# FreedomFighterPif.net
KiCad netlist of a schematic drawn in EAGLE
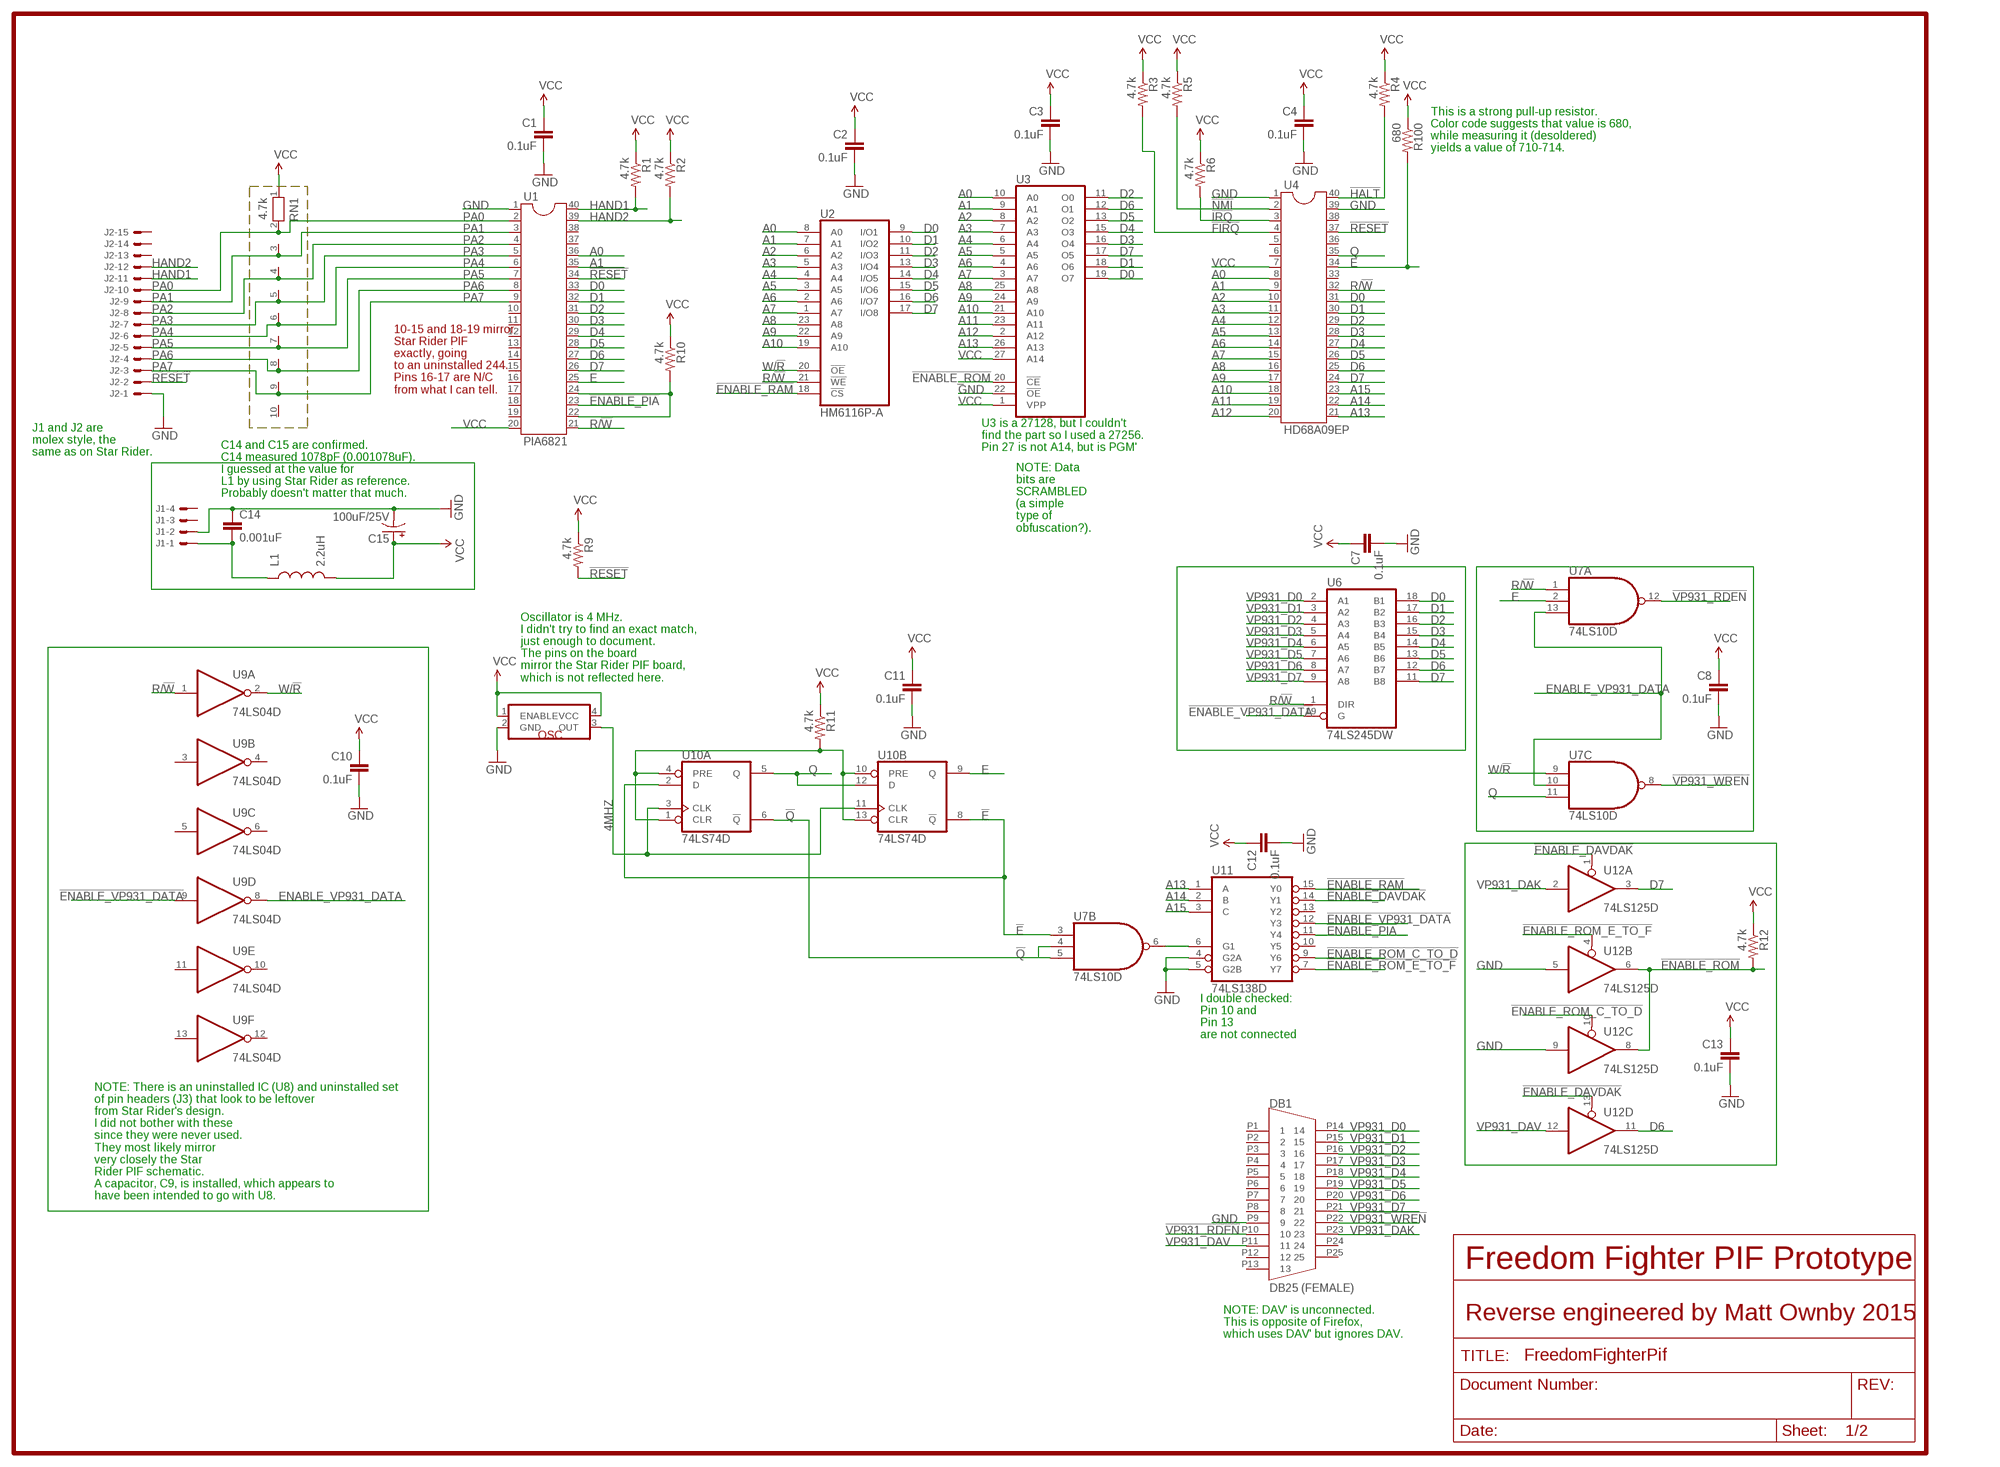
[diagram p0: schematic, sheet 1]
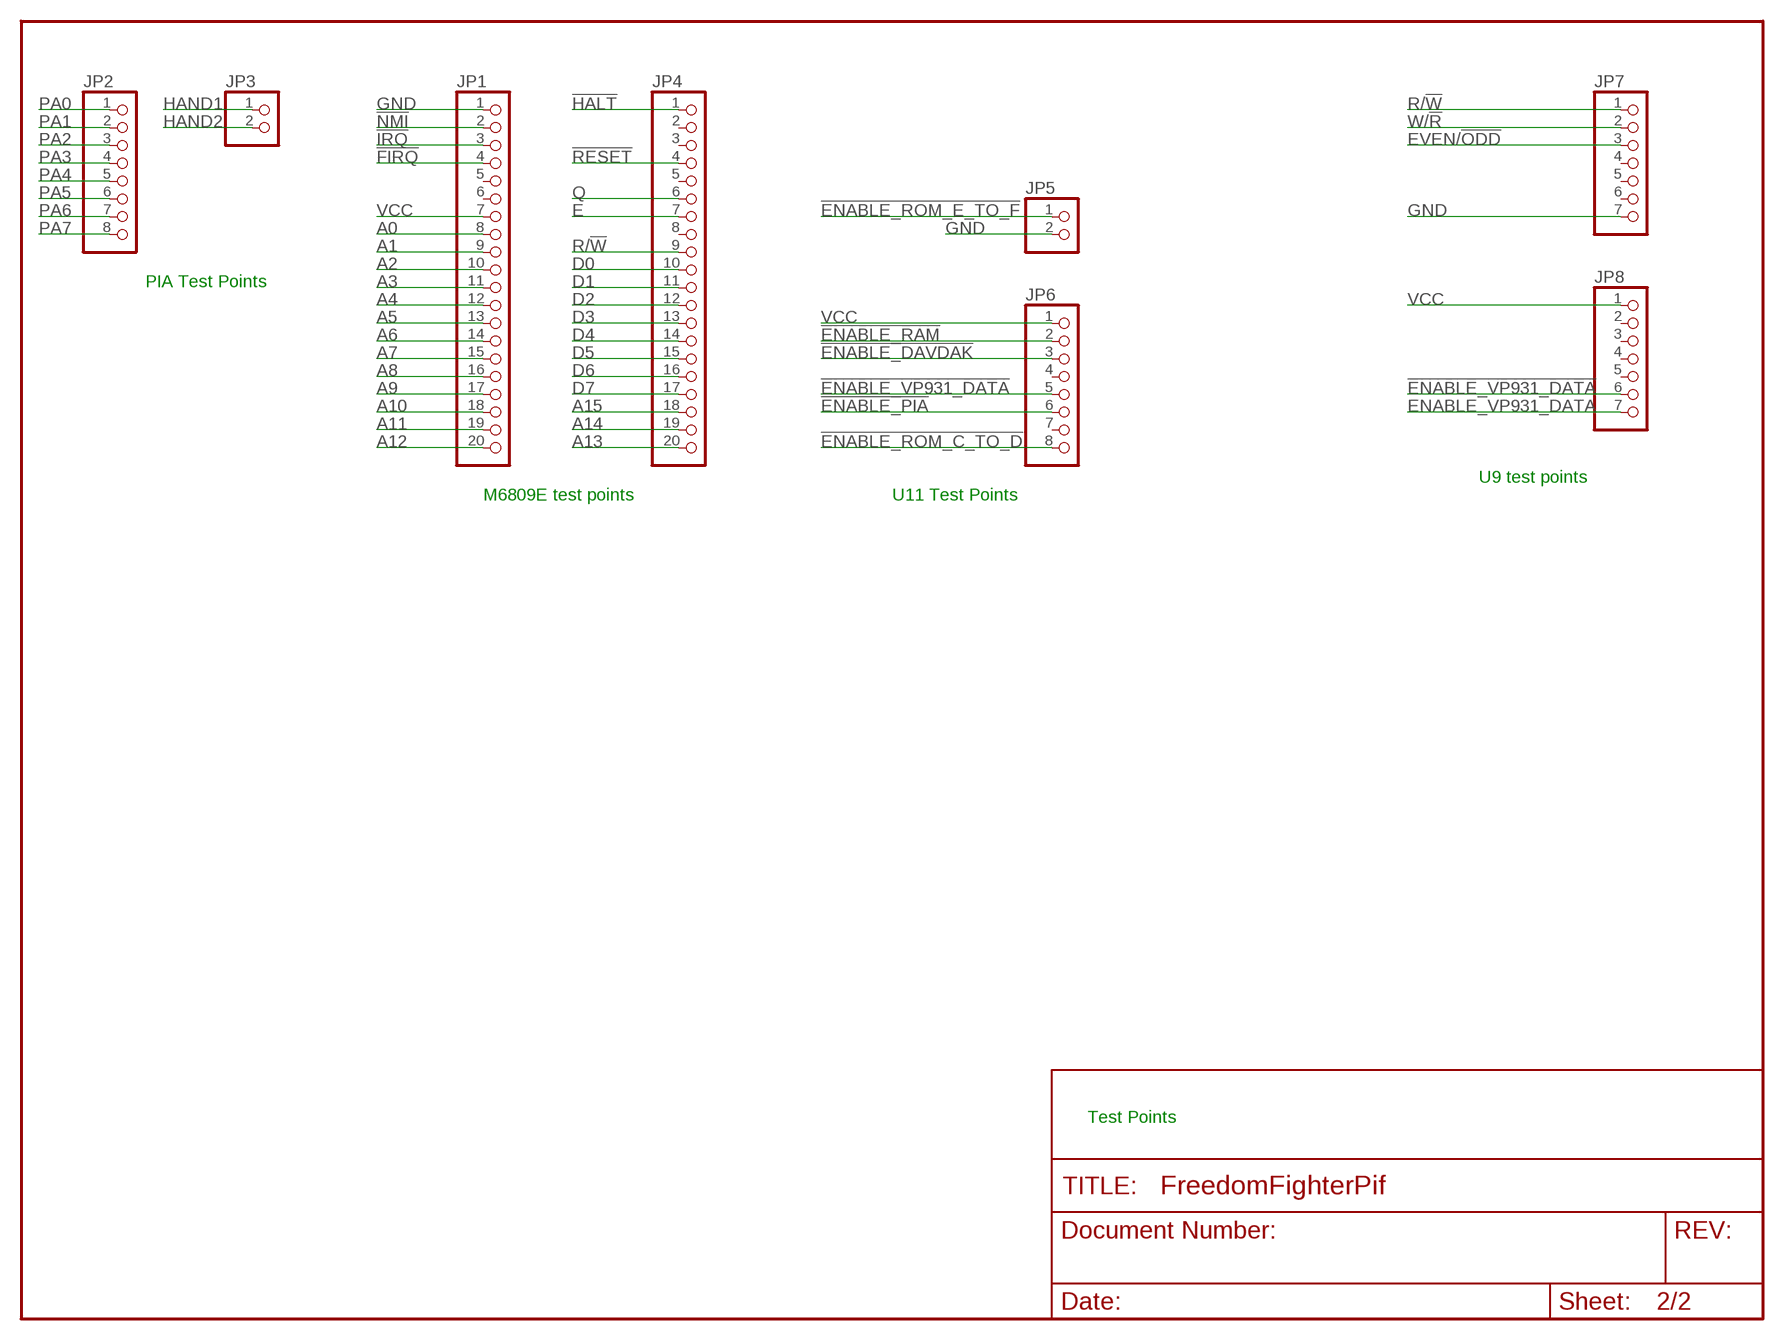
[diagram p1: schematic, sheet 2]

(export (version "E")
  (design (tool "Eeschema 10.0.6"))
  (components
    (comp (ref "JP1")
      (value "PINHD-1X20")
      (footprint "eagle-import:1X20")
      (libsource (lib "eagle-import") (part "PINHD-1X20"))
    )
    (comp (ref "JP2")
      (value "PINHD-1X8")
      (footprint "eagle-import:1X08")
      (libsource (lib "eagle-import") (part "PINHD-1X8"))
    )
    (comp (ref "JP3")
      (value "PINHD-1X2")
      (footprint "eagle-import:1X02")
      (libsource (lib "eagle-import") (part "PINHD-1X2"))
    )
    (comp (ref "JP4")
      (value "PINHD-1X20")
      (footprint "eagle-import:1X20")
      (libsource (lib "eagle-import") (part "PINHD-1X20"))
    )
    (comp (ref "JP5")
      (value "PINHD-1X2")
      (footprint "eagle-import:1X02")
      (libsource (lib "eagle-import") (part "PINHD-1X2"))
    )
    (comp (ref "JP6")
      (value "PINHD-1X8")
      (footprint "eagle-import:1X08")
      (libsource (lib "eagle-import") (part "PINHD-1X8"))
    )
    (comp (ref "JP7")
      (value "PINHD-1X7")
      (footprint "eagle-import:1X07")
      (libsource (lib "eagle-import") (part "PINHD-1X7"))
    )
    (comp (ref "JP8")
      (value "PINHD-1X7")
      (footprint "eagle-import:1X07")
      (libsource (lib "eagle-import") (part "PINHD-1X7"))
    )
    (comp (ref "C1")
      (value "0.1uF")
      (footprint "eagle-import:1206")
      (libsource (lib "eagle-import") (part "CAP1206"))
    )
    (comp (ref "C2")
      (value "0.1uF")
      (footprint "eagle-import:1206")
      (libsource (lib "eagle-import") (part "CAP1206"))
    )
    (comp (ref "C3")
      (value "0.1uF")
      (footprint "eagle-import:1206")
      (libsource (lib "eagle-import") (part "CAP1206"))
    )
    (comp (ref "C4")
      (value "0.1uF")
      (footprint "eagle-import:1206")
      (libsource (lib "eagle-import") (part "CAP1206"))
    )
    (comp (ref "C7")
      (value "0.1uF")
      (footprint "eagle-import:1206")
      (libsource (lib "eagle-import") (part "CAP1206"))
    )
    (comp (ref "C8")
      (value "0.1uF")
      (footprint "eagle-import:1206")
      (libsource (lib "eagle-import") (part "CAP1206"))
    )
    (comp (ref "C10")
      (value "0.1uF")
      (footprint "eagle-import:1206")
      (libsource (lib "eagle-import") (part "CAP1206"))
    )
    (comp (ref "C11")
      (value "0.1uF")
      (footprint "eagle-import:1206")
      (libsource (lib "eagle-import") (part "CAP1206"))
    )
    (comp (ref "C12")
      (value "0.1uF")
      (footprint "eagle-import:1206")
      (libsource (lib "eagle-import") (part "CAP1206"))
    )
    (comp (ref "C13")
      (value "0.1uF")
      (footprint "eagle-import:1206")
      (libsource (lib "eagle-import") (part "CAP1206"))
    )
    (comp (ref "C14")
      (value "0.001uF")
      (footprint "eagle-import:1206")
      (libsource (lib "eagle-import") (part "CAP1206"))
    )
    (comp (ref "C15")
      (value "100uF/25V")
      (footprint "eagle-import:CPOL-RADIAL-10UF-25V")
      (libsource (lib "eagle-import") (part "CAP_POLPTH2"))
    )
    (comp (ref "DB1")
      (value "DB25 (FEMALE)")
      (footprint "eagle-import:A32077-ND")
      (libsource (lib "eagle-import") (part "A32077-ND"))
    )
    (comp (ref "J1")
      (value "KK-156-4")
      (footprint "eagle-import:KK-156-4")
      (libsource (lib "eagle-import") (part "KK-156-4"))
    )
    (comp (ref "J2")
      (value "KK-156-15")
      (footprint "eagle-import:KK-156-15")
      (libsource (lib "eagle-import") (part "KK-156-15"))
    )
    (comp (ref "L1")
      (value "2.2uH")
      (footprint "eagle-import:INDUCTOR-1206")
      (libsource (lib "eagle-import") (part "INDUCTORH1206"))
    )
    (comp (ref "R1")
      (value "4.7k")
      (footprint "eagle-import:1206")
      (libsource (lib "eagle-import") (part "RESISTOR1206"))
    )
    (comp (ref "R2")
      (value "4.7k")
      (footprint "eagle-import:1206")
      (libsource (lib "eagle-import") (part "RESISTOR1206"))
    )
    (comp (ref "R3")
      (value "4.7k")
      (footprint "eagle-import:1206")
      (libsource (lib "eagle-import") (part "RESISTOR1206"))
    )
    (comp (ref "R4")
      (value "4.7k")
      (footprint "eagle-import:1206")
      (libsource (lib "eagle-import") (part "RESISTOR1206"))
    )
    (comp (ref "R5")
      (value "4.7k")
      (footprint "eagle-import:1206")
      (libsource (lib "eagle-import") (part "RESISTOR1206"))
    )
    (comp (ref "R6")
      (value "4.7k")
      (footprint "eagle-import:1206")
      (libsource (lib "eagle-import") (part "RESISTOR1206"))
    )
    (comp (ref "R9")
      (value "4.7k")
      (footprint "eagle-import:1206")
      (libsource (lib "eagle-import") (part "RESISTOR1206"))
    )
    (comp (ref "R10")
      (value "4.7k")
      (footprint "eagle-import:1206")
      (libsource (lib "eagle-import") (part "RESISTOR1206"))
    )
    (comp (ref "R11")
      (value "4.7k")
      (footprint "eagle-import:1206")
      (libsource (lib "eagle-import") (part "RESISTOR1206"))
    )
    (comp (ref "R12")
      (value "4.7k")
      (footprint "eagle-import:1206")
      (libsource (lib "eagle-import") (part "RESISTOR1206"))
    )
    (comp (ref "R100")
      (value "680")
      (footprint "eagle-import:1206")
      (libsource (lib "eagle-import") (part "RESISTOR1206"))
    )
    (comp (ref "RN1")
      (value "4.7k")
      (footprint "eagle-import:RN-10")
      (libsource (lib "eagle-import") (part "RN09"))
    )
    (comp (ref "U$1")
      (value "OSCILLATOR-SMT4")
      (footprint "eagle-import:SMT4-7MMX5MM")
      (libsource (lib "eagle-import") (part "OSCILLATOR-SMT4"))
    )
    (comp (ref "U1")
      (value "PIA6821")
      (footprint "eagle-import:DIL40")
      (libsource (lib "eagle-import") (part "DIL40"))
    )
    (comp (ref "U2")
      (value "HM6116P-A")
      (footprint "eagle-import:SO24-2")
      (libsource (lib "eagle-import") (part "6116S"))
    )
    (comp (ref "U3")
      (value "27256")
      (footprint "eagle-import:DIL28")
      (libsource (lib "eagle-import") (part "27256"))
    )
    (comp (ref "U4")
      (value "HD68A09EP")
      (footprint "eagle-import:DIL40")
      (libsource (lib "eagle-import") (part "DIL40"))
    )
    (comp (ref "U6")
      (value "74LS245DW")
      (footprint "eagle-import:SO20W")
      (libsource (lib "eagle-import") (part "74245DWLS"))
    )
    (comp (ref "U7")
      (value "74LS10D")
      (footprint "eagle-import:SO14")
      (libsource (lib "eagle-import") (part "7410DLS"))
    )
    (comp (ref "U9")
      (value "74LS04D")
      (footprint "eagle-import:SO14")
      (libsource (lib "eagle-import") (part "7404DLS"))
    )
    (comp (ref "U10")
      (value "74LS74D")
      (footprint "eagle-import:SO14")
      (libsource (lib "eagle-import") (part "7474DLS"))
    )
    (comp (ref "U11")
      (value "74LS138D")
      (footprint "eagle-import:SO16")
      (libsource (lib "eagle-import") (part "74138DLS"))
    )
    (comp (ref "U12")
      (value "74LS125D")
      (footprint "eagle-import:SO14")
      (libsource (lib "eagle-import") (part "74125DLS"))
    )
  )
  (nets
    (net (code "1") (name "4MHZ") (class "Default")
      (node (ref "U$1") (pin "3") (pinfunction "OUT_3") (pintype "output"))
      (node (ref "U10") (pin "11") (pinfunction "CLK_11") (pintype "input"))
      (node (ref "U10") (pin "3") (pinfunction "CLK_3") (pintype "input"))
    )
    (net (code "2") (name "A0") (class "Default")
      (node (ref "JP1") (pin "8") (pinfunction "8_8") (pintype "passive"))
      (node (ref "U1") (pin "36") (pinfunction "36_36") (pintype "passive"))
      (node (ref "U2") (pin "8") (pinfunction "A0_8") (pintype "input"))
      (node (ref "U3") (pin "10") (pinfunction "A0_10") (pintype "input"))
      (node (ref "U4") (pin "8") (pinfunction "8_8") (pintype "passive"))
    )
    (net (code "3") (name "A1") (class "Default")
      (node (ref "JP1") (pin "9") (pinfunction "9_9") (pintype "passive"))
      (node (ref "U1") (pin "35") (pinfunction "35_35") (pintype "passive"))
      (node (ref "U2") (pin "7") (pinfunction "A1_7") (pintype "input"))
      (node (ref "U3") (pin "9") (pinfunction "A1_9") (pintype "input"))
      (node (ref "U4") (pin "9") (pinfunction "9_9") (pintype "passive"))
    )
    (net (code "4") (name "A2") (class "Default")
      (node (ref "JP1") (pin "10") (pinfunction "10_10") (pintype "passive"))
      (node (ref "U2") (pin "6") (pinfunction "A2_6") (pintype "input"))
      (node (ref "U3") (pin "8") (pinfunction "A2_8") (pintype "input"))
      (node (ref "U4") (pin "10") (pinfunction "10_10") (pintype "passive"))
    )
    (net (code "5") (name "A3") (class "Default")
      (node (ref "JP1") (pin "11") (pinfunction "11_11") (pintype "passive"))
      (node (ref "U2") (pin "5") (pinfunction "A3_5") (pintype "input"))
      (node (ref "U3") (pin "7") (pinfunction "A3_7") (pintype "input"))
      (node (ref "U4") (pin "11") (pinfunction "11_11") (pintype "passive"))
    )
    (net (code "6") (name "A4") (class "Default")
      (node (ref "JP1") (pin "12") (pinfunction "12_12") (pintype "passive"))
      (node (ref "U2") (pin "4") (pinfunction "A4_4") (pintype "input"))
      (node (ref "U3") (pin "6") (pinfunction "A4_6") (pintype "input"))
      (node (ref "U4") (pin "12") (pinfunction "12_12") (pintype "passive"))
    )
    (net (code "7") (name "A5") (class "Default")
      (node (ref "JP1") (pin "13") (pinfunction "13_13") (pintype "passive"))
      (node (ref "U2") (pin "3") (pinfunction "A5_3") (pintype "input"))
      (node (ref "U3") (pin "5") (pinfunction "A5_5") (pintype "input"))
      (node (ref "U4") (pin "13") (pinfunction "13_13") (pintype "passive"))
    )
    (net (code "8") (name "A6") (class "Default")
      (node (ref "JP1") (pin "14") (pinfunction "14_14") (pintype "passive"))
      (node (ref "U2") (pin "2") (pinfunction "A6_2") (pintype "input"))
      (node (ref "U3") (pin "4") (pinfunction "A6_4") (pintype "input"))
      (node (ref "U4") (pin "14") (pinfunction "14_14") (pintype "passive"))
    )
    (net (code "9") (name "A7") (class "Default")
      (node (ref "JP1") (pin "15") (pinfunction "15_15") (pintype "passive"))
      (node (ref "U2") (pin "1") (pinfunction "A7_1") (pintype "input"))
      (node (ref "U3") (pin "3") (pinfunction "A7_3") (pintype "input"))
      (node (ref "U4") (pin "15") (pinfunction "15_15") (pintype "passive"))
    )
    (net (code "10") (name "A8") (class "Default")
      (node (ref "JP1") (pin "16") (pinfunction "16_16") (pintype "passive"))
      (node (ref "U2") (pin "23") (pinfunction "A8_23") (pintype "input"))
      (node (ref "U3") (pin "25") (pinfunction "A8_25") (pintype "input"))
      (node (ref "U4") (pin "16") (pinfunction "16_16") (pintype "passive"))
    )
    (net (code "11") (name "A9") (class "Default")
      (node (ref "JP1") (pin "17") (pinfunction "17_17") (pintype "passive"))
      (node (ref "U2") (pin "22") (pinfunction "A9_22") (pintype "input"))
      (node (ref "U3") (pin "24") (pinfunction "A9_24") (pintype "input"))
      (node (ref "U4") (pin "17") (pinfunction "17_17") (pintype "passive"))
    )
    (net (code "12") (name "A10") (class "Default")
      (node (ref "JP1") (pin "18") (pinfunction "18_18") (pintype "passive"))
      (node (ref "U2") (pin "19") (pinfunction "A10_19") (pintype "input"))
      (node (ref "U3") (pin "21") (pinfunction "A10_21") (pintype "input"))
      (node (ref "U4") (pin "18") (pinfunction "18_18") (pintype "passive"))
    )
    (net (code "13") (name "A11") (class "Default")
      (node (ref "JP1") (pin "19") (pinfunction "19_19") (pintype "passive"))
      (node (ref "U3") (pin "23") (pinfunction "A11_23") (pintype "input"))
      (node (ref "U4") (pin "19") (pinfunction "19_19") (pintype "passive"))
    )
    (net (code "14") (name "A12") (class "Default")
      (node (ref "JP1") (pin "20") (pinfunction "20_20") (pintype "passive"))
      (node (ref "U3") (pin "2") (pinfunction "A12_2") (pintype "input"))
      (node (ref "U4") (pin "20") (pinfunction "20_20") (pintype "passive"))
    )
    (net (code "15") (name "A13") (class "Default")
      (node (ref "JP4") (pin "20") (pinfunction "20_20") (pintype "passive"))
      (node (ref "U11") (pin "1") (pinfunction "A_1") (pintype "input"))
      (node (ref "U3") (pin "26") (pinfunction "A13_26") (pintype "input"))
      (node (ref "U4") (pin "21") (pinfunction "21_21") (pintype "passive"))
    )
    (net (code "16") (name "A14") (class "Default")
      (node (ref "JP4") (pin "19") (pinfunction "19_19") (pintype "passive"))
      (node (ref "U11") (pin "2") (pinfunction "B_2") (pintype "input"))
      (node (ref "U4") (pin "22") (pinfunction "22_22") (pintype "passive"))
    )
    (net (code "17") (name "A15") (class "Default")
      (node (ref "JP4") (pin "18") (pinfunction "18_18") (pintype "passive"))
      (node (ref "U11") (pin "3") (pinfunction "C_3") (pintype "input"))
      (node (ref "U4") (pin "23") (pinfunction "23_23") (pintype "passive"))
    )
    (net (code "18") (name "D0") (class "Default")
      (node (ref "JP4") (pin "10") (pinfunction "10_10") (pintype "passive"))
      (node (ref "U1") (pin "33") (pinfunction "33_33") (pintype "passive"))
      (node (ref "U2") (pin "9") (pinfunction "I/O1_9") (pintype "bidirectional"))
      (node (ref "U3") (pin "19") (pinfunction "O7_19") (pintype "tri_state"))
      (node (ref "U4") (pin "31") (pinfunction "31_31") (pintype "passive"))
      (node (ref "U6") (pin "18") (pinfunction "B1_18") (pintype "bidirectional"))
    )
    (net (code "19") (name "D1") (class "Default")
      (node (ref "JP4") (pin "11") (pinfunction "11_11") (pintype "passive"))
      (node (ref "U1") (pin "32") (pinfunction "32_32") (pintype "passive"))
      (node (ref "U2") (pin "10") (pinfunction "I/O2_10") (pintype "bidirectional"))
      (node (ref "U3") (pin "18") (pinfunction "O6_18") (pintype "tri_state"))
      (node (ref "U4") (pin "30") (pinfunction "30_30") (pintype "passive"))
      (node (ref "U6") (pin "17") (pinfunction "B2_17") (pintype "bidirectional"))
    )
    (net (code "20") (name "D2") (class "Default")
      (node (ref "JP4") (pin "12") (pinfunction "12_12") (pintype "passive"))
      (node (ref "U1") (pin "31") (pinfunction "31_31") (pintype "passive"))
      (node (ref "U2") (pin "11") (pinfunction "I/O3_11") (pintype "bidirectional"))
      (node (ref "U3") (pin "11") (pinfunction "O0_11") (pintype "tri_state"))
      (node (ref "U4") (pin "29") (pinfunction "29_29") (pintype "passive"))
      (node (ref "U6") (pin "16") (pinfunction "B3_16") (pintype "bidirectional"))
    )
    (net (code "21") (name "D3") (class "Default")
      (node (ref "JP4") (pin "13") (pinfunction "13_13") (pintype "passive"))
      (node (ref "U1") (pin "30") (pinfunction "30_30") (pintype "passive"))
      (node (ref "U2") (pin "13") (pinfunction "I/O4_13") (pintype "bidirectional"))
      (node (ref "U3") (pin "16") (pinfunction "O4_16") (pintype "tri_state"))
      (node (ref "U4") (pin "28") (pinfunction "28_28") (pintype "passive"))
      (node (ref "U6") (pin "15") (pinfunction "B4_15") (pintype "bidirectional"))
    )
    (net (code "22") (name "D4") (class "Default")
      (node (ref "JP4") (pin "14") (pinfunction "14_14") (pintype "passive"))
      (node (ref "U1") (pin "29") (pinfunction "29_29") (pintype "passive"))
      (node (ref "U2") (pin "14") (pinfunction "I/O5_14") (pintype "bidirectional"))
      (node (ref "U3") (pin "15") (pinfunction "O3_15") (pintype "tri_state"))
      (node (ref "U4") (pin "27") (pinfunction "27_27") (pintype "passive"))
      (node (ref "U6") (pin "14") (pinfunction "B5_14") (pintype "bidirectional"))
    )
    (net (code "23") (name "D5") (class "Default")
      (node (ref "JP4") (pin "15") (pinfunction "15_15") (pintype "passive"))
      (node (ref "U1") (pin "28") (pinfunction "28_28") (pintype "passive"))
      (node (ref "U2") (pin "15") (pinfunction "I/O6_15") (pintype "bidirectional"))
      (node (ref "U3") (pin "13") (pinfunction "O2_13") (pintype "tri_state"))
      (node (ref "U4") (pin "26") (pinfunction "26_26") (pintype "passive"))
      (node (ref "U6") (pin "13") (pinfunction "B6_13") (pintype "bidirectional"))
    )
    (net (code "24") (name "D6") (class "Default")
      (node (ref "JP4") (pin "16") (pinfunction "16_16") (pintype "passive"))
      (node (ref "U1") (pin "27") (pinfunction "27_27") (pintype "passive"))
      (node (ref "U12") (pin "11") (pinfunction "O_11") (pintype "tri_state"))
      (node (ref "U2") (pin "16") (pinfunction "I/O7_16") (pintype "bidirectional"))
      (node (ref "U3") (pin "12") (pinfunction "O1_12") (pintype "tri_state"))
      (node (ref "U4") (pin "25") (pinfunction "25_25") (pintype "passive"))
      (node (ref "U6") (pin "12") (pinfunction "B7_12") (pintype "bidirectional"))
    )
    (net (code "25") (name "D7") (class "Default")
      (node (ref "JP4") (pin "17") (pinfunction "17_17") (pintype "passive"))
      (node (ref "U1") (pin "26") (pinfunction "26_26") (pintype "passive"))
      (node (ref "U12") (pin "3") (pinfunction "O_3") (pintype "tri_state"))
      (node (ref "U2") (pin "17") (pinfunction "I/O8_17") (pintype "bidirectional"))
      (node (ref "U3") (pin "17") (pinfunction "O5_17") (pintype "tri_state"))
      (node (ref "U4") (pin "24") (pinfunction "24_24") (pintype "passive"))
      (node (ref "U6") (pin "11") (pinfunction "B8_11") (pintype "bidirectional"))
    )
    (net (code "26") (name "E") (class "Default")
      (node (ref "JP4") (pin "7") (pinfunction "7_7") (pintype "passive"))
      (node (ref "R100") (pin "2") (pinfunction "2_2") (pintype "passive"))
      (node (ref "U1") (pin "25") (pinfunction "25_25") (pintype "passive"))
      (node (ref "U10") (pin "9") (pinfunction "Q_9") (pintype "output"))
      (node (ref "U4") (pin "34") (pinfunction "34_34") (pintype "passive"))
      (node (ref "U7") (pin "2") (pinfunction "I1_2") (pintype "input"))
    )
    (net (code "27") (name "ENABLE_VP931_DATA") (class "Default")
      (node (ref "JP8") (pin "7") (pinfunction "7_7") (pintype "passive"))
      (node (ref "U7") (pin "10") (pinfunction "I1_10") (pintype "input"))
      (node (ref "U7") (pin "13") (pinfunction "I2_13") (pintype "input"))
      (node (ref "U9") (pin "8") (pinfunction "O_8") (pintype "output"))
    )
    (net (code "28") (name "EVEN{slash}~{ODD}") (class "Default")
      (node (ref "JP7") (pin "3") (pinfunction "3_3") (pintype "passive"))
    )
    (net (code "29") (name "GND") (class "Default")
      (node (ref "C1") (pin "2") (pinfunction "2_2") (pintype "passive"))
      (node (ref "C10") (pin "2") (pinfunction "2_2") (pintype "passive"))
      (node (ref "C11") (pin "2") (pinfunction "2_2") (pintype "passive"))
      (node (ref "C12") (pin "2") (pinfunction "2_2") (pintype "passive"))
      (node (ref "C13") (pin "2") (pinfunction "2_2") (pintype "passive"))
      (node (ref "C14") (pin "1") (pinfunction "1_1") (pintype "passive"))
      (node (ref "C15") (pin "2") (pinfunction "-_2") (pintype "passive"))
      (node (ref "C2") (pin "2") (pinfunction "2_2") (pintype "passive"))
      (node (ref "C3") (pin "2") (pinfunction "2_2") (pintype "passive"))
      (node (ref "C4") (pin "2") (pinfunction "2_2") (pintype "passive"))
      (node (ref "C7") (pin "2") (pinfunction "2_2") (pintype "passive"))
      (node (ref "C8") (pin "2") (pinfunction "2_2") (pintype "passive"))
      (node (ref "DB1") (pin "P9") (pinfunction "9_P9") (pintype "bidirectional"))
      (node (ref "J1") (pin "2") (pinfunction "S_2") (pintype "passive"))
      (node (ref "J2") (pin "1") (pinfunction "S_1") (pintype "passive"))
      (node (ref "JP1") (pin "1") (pinfunction "1_1") (pintype "passive"))
      (node (ref "JP5") (pin "2") (pinfunction "2_2") (pintype "passive"))
      (node (ref "JP7") (pin "7") (pinfunction "7_7") (pintype "passive"))
      (node (ref "U$1") (pin "2") (pinfunction "GND_2") (pintype "power_in"))
      (node (ref "U1") (pin "1") (pinfunction "1_1") (pintype "passive"))
      (node (ref "U11") (pin "4") (pinfunction "G2A_4") (pintype "input"))
      (node (ref "U11") (pin "5") (pinfunction "G2B_5") (pintype "input"))
      (node (ref "U12") (pin "5") (pinfunction "I_5") (pintype "input"))
      (node (ref "U12") (pin "9") (pinfunction "I_9") (pintype "input"))
      (node (ref "U3") (pin "22") (pinfunction "~{OE}_22") (pintype "input"))
      (node (ref "U4") (pin "1") (pinfunction "1_1") (pintype "passive"))
      (node (ref "U4") (pin "39") (pinfunction "39_39") (pintype "passive"))
    )
    (net (code "30") (name "HAND1") (class "Default")
      (node (ref "J2") (pin "11") (pinfunction "S_11") (pintype "passive"))
      (node (ref "JP3") (pin "1") (pinfunction "1_1") (pintype "passive"))
      (node (ref "R1") (pin "2") (pinfunction "2_2") (pintype "passive"))
      (node (ref "U1") (pin "40") (pinfunction "40_40") (pintype "passive"))
    )
    (net (code "31") (name "HAND2") (class "Default")
      (node (ref "J2") (pin "12") (pinfunction "S_12") (pintype "passive"))
      (node (ref "JP3") (pin "2") (pinfunction "2_2") (pintype "passive"))
      (node (ref "R2") (pin "2") (pinfunction "2_2") (pintype "passive"))
      (node (ref "U1") (pin "39") (pinfunction "39_39") (pintype "passive"))
    )
    (net (code "32") (name "Net-(J1A-S)") (class "Default")
      (node (ref "C14") (pin "2") (pinfunction "2_2") (pintype "passive"))
      (node (ref "J1") (pin "1") (pinfunction "S_1") (pintype "passive"))
      (node (ref "L1") (pin "P$1") (pinfunction "1_P$1") (pintype "passive"))
    )
    (net (code "33") (name "Net-(R10-Pad2)") (class "Default")
      (node (ref "R10") (pin "2") (pinfunction "2_2") (pintype "passive"))
      (node (ref "U1") (pin "22") (pinfunction "22_22") (pintype "passive"))
      (node (ref "U1") (pin "24") (pinfunction "24_24") (pintype "passive"))
    )
    (net (code "34") (name "Net-(U10A-CLR)") (class "Default")
      (node (ref "R11") (pin "2") (pinfunction "2_2") (pintype "passive"))
      (node (ref "U10") (pin "1") (pinfunction "CLR_1") (pintype "input"))
      (node (ref "U10") (pin "10") (pinfunction "PRE_10") (pintype "input"))
      (node (ref "U10") (pin "13") (pinfunction "CLR_13") (pintype "input"))
      (node (ref "U10") (pin "4") (pinfunction "PRE_4") (pintype "input"))
    )
    (net (code "35") (name "Net-(U11A-G1)") (class "Default")
      (node (ref "U11") (pin "6") (pinfunction "G1_6") (pintype "input"))
      (node (ref "U7") (pin "6") (pinfunction "O_6") (pintype "output"))
    )
    (net (code "36") (name "PA0") (class "Default")
      (node (ref "J2") (pin "10") (pinfunction "S_10") (pintype "passive"))
      (node (ref "JP2") (pin "1") (pinfunction "1_1") (pintype "passive"))
      (node (ref "RN1") (pin "2") (pinfunction "2_2") (pintype "passive"))
      (node (ref "U1") (pin "2") (pinfunction "2_2") (pintype "passive"))
    )
    (net (code "37") (name "PA1") (class "Default")
      (node (ref "J2") (pin "9") (pinfunction "S_9") (pintype "passive"))
      (node (ref "JP2") (pin "2") (pinfunction "2_2") (pintype "passive"))
      (node (ref "RN1") (pin "3") (pinfunction "3_3") (pintype "passive"))
      (node (ref "U1") (pin "3") (pinfunction "3_3") (pintype "passive"))
    )
    (net (code "38") (name "PA2") (class "Default")
      (node (ref "J2") (pin "8") (pinfunction "S_8") (pintype "passive"))
      (node (ref "JP2") (pin "3") (pinfunction "3_3") (pintype "passive"))
      (node (ref "RN1") (pin "4") (pinfunction "4_4") (pintype "passive"))
      (node (ref "U1") (pin "4") (pinfunction "4_4") (pintype "passive"))
    )
    (net (code "39") (name "PA3") (class "Default")
      (node (ref "J2") (pin "7") (pinfunction "S_7") (pintype "passive"))
      (node (ref "JP2") (pin "4") (pinfunction "4_4") (pintype "passive"))
      (node (ref "RN1") (pin "5") (pinfunction "5_5") (pintype "passive"))
      (node (ref "U1") (pin "5") (pinfunction "5_5") (pintype "passive"))
    )
    (net (code "40") (name "PA4") (class "Default")
      (node (ref "J2") (pin "6") (pinfunction "S_6") (pintype "passive"))
      (node (ref "JP2") (pin "5") (pinfunction "5_5") (pintype "passive"))
      (node (ref "RN1") (pin "6") (pinfunction "6_6") (pintype "passive"))
      (node (ref "U1") (pin "6") (pinfunction "6_6") (pintype "passive"))
    )
    (net (code "41") (name "PA5") (class "Default")
      (node (ref "J2") (pin "5") (pinfunction "S_5") (pintype "passive"))
      (node (ref "JP2") (pin "6") (pinfunction "6_6") (pintype "passive"))
      (node (ref "RN1") (pin "7") (pinfunction "7_7") (pintype "passive"))
      (node (ref "U1") (pin "7") (pinfunction "7_7") (pintype "passive"))
    )
    (net (code "42") (name "PA6") (class "Default")
      (node (ref "J2") (pin "4") (pinfunction "S_4") (pintype "passive"))
      (node (ref "JP2") (pin "7") (pinfunction "7_7") (pintype "passive"))
      (node (ref "RN1") (pin "8") (pinfunction "8_8") (pintype "passive"))
      (node (ref "U1") (pin "8") (pinfunction "8_8") (pintype "passive"))
    )
    (net (code "43") (name "PA7") (class "Default")
      (node (ref "J2") (pin "3") (pinfunction "S_3") (pintype "passive"))
      (node (ref "JP2") (pin "8") (pinfunction "8_8") (pintype "passive"))
      (node (ref "RN1") (pin "9") (pinfunction "9_9") (pintype "passive"))
      (node (ref "U1") (pin "9") (pinfunction "9_9") (pintype "passive"))
    )
    (net (code "44") (name "Q") (class "Default")
      (node (ref "JP4") (pin "6") (pinfunction "6_6") (pintype "passive"))
      (node (ref "U10") (pin "12") (pinfunction "D_12") (pintype "input"))
      (node (ref "U10") (pin "5") (pinfunction "Q_5") (pintype "output"))
      (node (ref "U4") (pin "35") (pinfunction "35_35") (pintype "passive"))
      (node (ref "U7") (pin "11") (pinfunction "I2_11") (pintype "input"))
    )
    (net (code "45") (name "R{slash}~{W}") (class "Default")
      (node (ref "JP4") (pin "9") (pinfunction "9_9") (pintype "passive"))
      (node (ref "JP7") (pin "1") (pinfunction "1_1") (pintype "passive"))
      (node (ref "U1") (pin "21") (pinfunction "21_21") (pintype "passive"))
      (node (ref "U2") (pin "21") (pinfunction "~{WE}_21") (pintype "input"))
      (node (ref "U4") (pin "32") (pinfunction "32_32") (pintype "passive"))
      (node (ref "U6") (pin "1") (pinfunction "DIR_1") (pintype "input"))
      (node (ref "U7") (pin "1") (pinfunction "I0_1") (pintype "input"))
      (node (ref "U9") (pin "1") (pinfunction "I_1") (pintype "input"))
    )
    (net (code "46") (name "VCC") (class "Default")
      (node (ref "C1") (pin "1") (pinfunction "1_1") (pintype "passive"))
      (node (ref "C10") (pin "1") (pinfunction "1_1") (pintype "passive"))
      (node (ref "C11") (pin "1") (pinfunction "1_1") (pintype "passive"))
      (node (ref "C12") (pin "1") (pinfunction "1_1") (pintype "passive"))
      (node (ref "C13") (pin "1") (pinfunction "1_1") (pintype "passive"))
      (node (ref "C15") (pin "1") (pinfunction "+_1") (pintype "passive"))
      (node (ref "C2") (pin "1") (pinfunction "1_1") (pintype "passive"))
      (node (ref "C3") (pin "1") (pinfunction "1_1") (pintype "passive"))
      (node (ref "C4") (pin "1") (pinfunction "1_1") (pintype "passive"))
      (node (ref "C7") (pin "1") (pinfunction "1_1") (pintype "passive"))
      (node (ref "C8") (pin "1") (pinfunction "1_1") (pintype "passive"))
      (node (ref "JP1") (pin "7") (pinfunction "7_7") (pintype "passive"))
      (node (ref "JP6") (pin "1") (pinfunction "1_1") (pintype "passive"))
      (node (ref "JP8") (pin "1") (pinfunction "1_1") (pintype "passive"))
      (node (ref "L1") (pin "P$2") (pinfunction "2_P$2") (pintype "passive"))
      (node (ref "R1") (pin "1") (pinfunction "1_1") (pintype "passive"))
      (node (ref "R10") (pin "1") (pinfunction "1_1") (pintype "passive"))
      (node (ref "R100") (pin "1") (pinfunction "1_1") (pintype "passive"))
      (node (ref "R11") (pin "1") (pinfunction "1_1") (pintype "passive"))
      (node (ref "R12") (pin "1") (pinfunction "1_1") (pintype "passive"))
      (node (ref "R2") (pin "1") (pinfunction "1_1") (pintype "passive"))
      (node (ref "R3") (pin "1") (pinfunction "1_1") (pintype "passive"))
      (node (ref "R4") (pin "1") (pinfunction "1_1") (pintype "passive"))
      (node (ref "R5") (pin "1") (pinfunction "1_1") (pintype "passive"))
      (node (ref "R6") (pin "1") (pinfunction "1_1") (pintype "passive"))
      (node (ref "R9") (pin "1") (pinfunction "1_1") (pintype "passive"))
      (node (ref "RN1") (pin "1") (pinfunction "1_1") (pintype "passive"))
      (node (ref "U$1") (pin "1") (pinfunction "ENABLE_1") (pintype "input"))
      (node (ref "U$1") (pin "4") (pinfunction "VCC_4") (pintype "power_in"))
      (node (ref "U1") (pin "20") (pinfunction "20_20") (pintype "passive"))
      (node (ref "U3") (pin "1") (pinfunction "VPP_1") (pintype "input"))
      (node (ref "U3") (pin "27") (pinfunction "A14_27") (pintype "input"))
      (node (ref "U4") (pin "7") (pinfunction "7_7") (pintype "passive"))
    )
    (net (code "47") (name "VP931_D0") (class "Default")
      (node (ref "DB1") (pin "P14") (pinfunction "14_P14") (pintype "bidirectional"))
      (node (ref "U6") (pin "2") (pinfunction "A1_2") (pintype "bidirectional"))
    )
    (net (code "48") (name "VP931_D1") (class "Default")
      (node (ref "DB1") (pin "P15") (pinfunction "15_P15") (pintype "bidirectional"))
      (node (ref "U6") (pin "3") (pinfunction "A2_3") (pintype "bidirectional"))
    )
    (net (code "49") (name "VP931_D2") (class "Default")
      (node (ref "DB1") (pin "P16") (pinfunction "16_P16") (pintype "bidirectional"))
      (node (ref "U6") (pin "4") (pinfunction "A3_4") (pintype "bidirectional"))
    )
    (net (code "50") (name "VP931_D3") (class "Default")
      (node (ref "DB1") (pin "P17") (pinfunction "17_P17") (pintype "bidirectional"))
      (node (ref "U6") (pin "5") (pinfunction "A4_5") (pintype "bidirectional"))
    )
    (net (code "51") (name "VP931_D4") (class "Default")
      (node (ref "DB1") (pin "P18") (pinfunction "18_P18") (pintype "bidirectional"))
      (node (ref "U6") (pin "6") (pinfunction "A5_6") (pintype "bidirectional"))
    )
    (net (code "52") (name "VP931_D5") (class "Default")
      (node (ref "DB1") (pin "P19") (pinfunction "19_P19") (pintype "bidirectional"))
      (node (ref "U6") (pin "7") (pinfunction "A6_7") (pintype "bidirectional"))
    )
    (net (code "53") (name "VP931_D6") (class "Default")
      (node (ref "DB1") (pin "P20") (pinfunction "20_P20") (pintype "bidirectional"))
      (node (ref "U6") (pin "8") (pinfunction "A7_8") (pintype "bidirectional"))
    )
    (net (code "54") (name "VP931_D7") (class "Default")
      (node (ref "DB1") (pin "P21") (pinfunction "21_P21") (pintype "bidirectional"))
      (node (ref "U6") (pin "9") (pinfunction "A8_9") (pintype "bidirectional"))
    )
    (net (code "55") (name "VP931_DAK") (class "Default")
      (node (ref "DB1") (pin "P23") (pinfunction "23_P23") (pintype "bidirectional"))
      (node (ref "U12") (pin "2") (pinfunction "I_2") (pintype "input"))
    )
    (net (code "56") (name "VP931_DAV") (class "Default")
      (node (ref "DB1") (pin "P11") (pinfunction "11_P11") (pintype "bidirectional"))
      (node (ref "U12") (pin "12") (pinfunction "I_12") (pintype "input"))
    )
    (net (code "57") (name "W{slash}~{R}") (class "Default")
      (node (ref "JP7") (pin "2") (pinfunction "2_2") (pintype "passive"))
      (node (ref "U2") (pin "20") (pinfunction "~{OE}_20") (pintype "input"))
      (node (ref "U7") (pin "9") (pinfunction "I0_9") (pintype "input"))
      (node (ref "U9") (pin "2") (pinfunction "O_2") (pintype "output"))
    )
    (net (code "58") (name "unconnected-(DB1-1-PadP1)") (class "Default")
      (node (ref "DB1") (pin "P1") (pinfunction "1_P1") (pintype "bidirectional"))
    )
    (net (code "59") (name "unconnected-(DB1-2-PadP2)") (class "Default")
      (node (ref "DB1") (pin "P2") (pinfunction "2_P2") (pintype "bidirectional"))
    )
    (net (code "60") (name "unconnected-(DB1-3-PadP3)") (class "Default")
      (node (ref "DB1") (pin "P3") (pinfunction "3_P3") (pintype "bidirectional"))
    )
    (net (code "61") (name "unconnected-(DB1-4-PadP4)") (class "Default")
      (node (ref "DB1") (pin "P4") (pinfunction "4_P4") (pintype "bidirectional"))
    )
    (net (code "62") (name "unconnected-(DB1-5-PadP5)") (class "Default")
      (node (ref "DB1") (pin "P5") (pinfunction "5_P5") (pintype "bidirectional"))
    )
    (net (code "63") (name "unconnected-(DB1-6-PadP6)") (class "Default")
      (node (ref "DB1") (pin "P6") (pinfunction "6_P6") (pintype "bidirectional"))
    )
    (net (code "64") (name "unconnected-(DB1-7-PadP7)") (class "Default")
      (node (ref "DB1") (pin "P7") (pinfunction "7_P7") (pintype "bidirectional"))
    )
    (net (code "65") (name "unconnected-(DB1-8-PadP8)") (class "Default")
      (node (ref "DB1") (pin "P8") (pinfunction "8_P8") (pintype "bidirectional"))
    )
    (net (code "66") (name "unconnected-(DB1-12-PadP12)") (class "Default")
      (node (ref "DB1") (pin "P12") (pinfunction "12_P12") (pintype "bidirectional"))
    )
    (net (code "67") (name "unconnected-(DB1-13-PadP13)") (class "Default")
      (node (ref "DB1") (pin "P13") (pinfunction "13_P13") (pintype "bidirectional"))
    )
    (net (code "68") (name "unconnected-(DB1-24-PadP24)") (class "Default")
      (node (ref "DB1") (pin "P24") (pinfunction "24_P24") (pintype "bidirectional"))
    )
    (net (code "69") (name "unconnected-(DB1-25-PadP25)") (class "Default")
      (node (ref "DB1") (pin "P25") (pinfunction "25_P25") (pintype "bidirectional"))
    )
    (net (code "70") (name "unconnected-(J1C-S-Pad3)") (class "Default")
      (node (ref "J1") (pin "3") (pinfunction "S_3") (pintype "passive"))
    )
    (net (code "71") (name "unconnected-(J1D-S-Pad4)") (class "Default")
      (node (ref "J1") (pin "4") (pinfunction "S_4") (pintype "passive"))
    )
    (net (code "72") (name "unconnected-(J2E-S-Pad13)") (class "Default")
      (node (ref "J2") (pin "13") (pinfunction "S_13") (pintype "passive"))
    )
    (net (code "73") (name "unconnected-(J2F-S-Pad14)") (class "Default")
      (node (ref "J2") (pin "14") (pinfunction "S_14") (pintype "passive"))
    )
    (net (code "74") (name "unconnected-(J2G-S-Pad15)") (class "Default")
      (node (ref "J2") (pin "15") (pinfunction "S_15") (pintype "passive"))
    )
    (net (code "75") (name "unconnected-(JP1-Pad5)") (class "Default")
      (node (ref "JP1") (pin "5") (pinfunction "5_5") (pintype "passive"))
    )
    (net (code "76") (name "unconnected-(JP1-Pad6)") (class "Default")
      (node (ref "JP1") (pin "6") (pinfunction "6_6") (pintype "passive"))
    )
    (net (code "77") (name "unconnected-(JP4-Pad2)") (class "Default")
      (node (ref "JP4") (pin "2") (pinfunction "2_2") (pintype "passive"))
    )
    (net (code "78") (name "unconnected-(JP4-Pad3)") (class "Default")
      (node (ref "JP4") (pin "3") (pinfunction "3_3") (pintype "passive"))
    )
    (net (code "79") (name "unconnected-(JP4-Pad5)") (class "Default")
      (node (ref "JP4") (pin "5") (pinfunction "5_5") (pintype "passive"))
    )
    (net (code "80") (name "unconnected-(JP4-Pad8)") (class "Default")
      (node (ref "JP4") (pin "8") (pinfunction "8_8") (pintype "passive"))
    )
    (net (code "81") (name "unconnected-(JP6-Pad4)") (class "Default")
      (node (ref "JP6") (pin "4") (pinfunction "4_4") (pintype "passive"))
    )
    (net (code "82") (name "unconnected-(JP6-Pad7)") (class "Default")
      (node (ref "JP6") (pin "7") (pinfunction "7_7") (pintype "passive"))
    )
    (net (code "83") (name "unconnected-(JP7-Pad4)") (class "Default")
      (node (ref "JP7") (pin "4") (pinfunction "4_4") (pintype "passive"))
    )
    (net (code "84") (name "unconnected-(JP7-Pad5)") (class "Default")
      (node (ref "JP7") (pin "5") (pinfunction "5_5") (pintype "passive"))
    )
    (net (code "85") (name "unconnected-(JP7-Pad6)") (class "Default")
      (node (ref "JP7") (pin "6") (pinfunction "6_6") (pintype "passive"))
    )
    (net (code "86") (name "unconnected-(JP8-Pad2)") (class "Default")
      (node (ref "JP8") (pin "2") (pinfunction "2_2") (pintype "passive"))
    )
    (net (code "87") (name "unconnected-(JP8-Pad3)") (class "Default")
      (node (ref "JP8") (pin "3") (pinfunction "3_3") (pintype "passive"))
    )
    (net (code "88") (name "unconnected-(JP8-Pad4)") (class "Default")
      (node (ref "JP8") (pin "4") (pinfunction "4_4") (pintype "passive"))
    )
    (net (code "89") (name "unconnected-(JP8-Pad5)") (class "Default")
      (node (ref "JP8") (pin "5") (pinfunction "5_5") (pintype "passive"))
    )
    (net (code "90") (name "unconnected-(RN1-Pad10)") (class "Default")
      (node (ref "RN1") (pin "10") (pinfunction "10_10") (pintype "passive"))
    )
    (net (code "91") (name "unconnected-(U1-Pad10)") (class "Default")
      (node (ref "U1") (pin "10") (pinfunction "10_10") (pintype "passive"))
    )
    (net (code "92") (name "unconnected-(U1-Pad11)") (class "Default")
      (node (ref "U1") (pin "11") (pinfunction "11_11") (pintype "passive"))
    )
    (net (code "93") (name "unconnected-(U1-Pad12)") (class "Default")
      (node (ref "U1") (pin "12") (pinfunction "12_12") (pintype "passive"))
    )
    (net (code "94") (name "unconnected-(U1-Pad13)") (class "Default")
      (node (ref "U1") (pin "13") (pinfunction "13_13") (pintype "passive"))
    )
    (net (code "95") (name "unconnected-(U1-Pad14)") (class "Default")
      (node (ref "U1") (pin "14") (pinfunction "14_14") (pintype "passive"))
    )
    (net (code "96") (name "unconnected-(U1-Pad15)") (class "Default")
      (node (ref "U1") (pin "15") (pinfunction "15_15") (pintype "passive"))
    )
    (net (code "97") (name "unconnected-(U1-Pad16)") (class "Default")
      (node (ref "U1") (pin "16") (pinfunction "16_16") (pintype "passive"))
    )
    (net (code "98") (name "unconnected-(U1-Pad17)") (class "Default")
      (node (ref "U1") (pin "17") (pinfunction "17_17") (pintype "passive"))
    )
    (net (code "99") (name "unconnected-(U1-Pad18)") (class "Default")
      (node (ref "U1") (pin "18") (pinfunction "18_18") (pintype "passive"))
    )
    (net (code "100") (name "unconnected-(U1-Pad19)") (class "Default")
      (node (ref "U1") (pin "19") (pinfunction "19_19") (pintype "passive"))
    )
    (net (code "101") (name "unconnected-(U1-Pad37)") (class "Default")
      (node (ref "U1") (pin "37") (pinfunction "37_37") (pintype "passive"))
    )
    (net (code "102") (name "unconnected-(U1-Pad38)") (class "Default")
      (node (ref "U1") (pin "38") (pinfunction "38_38") (pintype "passive"))
    )
    (net (code "103") (name "unconnected-(U4-Pad5)") (class "Default")
      (node (ref "U4") (pin "5") (pinfunction "5_5") (pintype "passive"))
    )
    (net (code "104") (name "unconnected-(U4-Pad6)") (class "Default")
      (node (ref "U4") (pin "6") (pinfunction "6_6") (pintype "passive"))
    )
    (net (code "105") (name "unconnected-(U4-Pad33)") (class "Default")
      (node (ref "U4") (pin "33") (pinfunction "33_33") (pintype "passive"))
    )
    (net (code "106") (name "unconnected-(U4-Pad36)") (class "Default")
      (node (ref "U4") (pin "36") (pinfunction "36_36") (pintype "passive"))
    )
    (net (code "107") (name "unconnected-(U4-Pad38)") (class "Default")
      (node (ref "U4") (pin "38") (pinfunction "38_38") (pintype "passive"))
    )
    (net (code "108") (name "unconnected-(U9B-I-Pad3)") (class "Default")
      (node (ref "U9") (pin "3") (pinfunction "I_3") (pintype "input"))
    )
    (net (code "109") (name "unconnected-(U9B-O-Pad4)") (class "Default")
      (node (ref "U9") (pin "4") (pinfunction "O_4") (pintype "output"))
    )
    (net (code "110") (name "unconnected-(U9C-I-Pad5)") (class "Default")
      (node (ref "U9") (pin "5") (pinfunction "I_5") (pintype "input"))
    )
    (net (code "111") (name "unconnected-(U9C-O-Pad6)") (class "Default")
      (node (ref "U9") (pin "6") (pinfunction "O_6") (pintype "output"))
    )
    (net (code "112") (name "unconnected-(U9E-I-Pad11)") (class "Default")
      (node (ref "U9") (pin "11") (pinfunction "I_11") (pintype "input"))
    )
    (net (code "113") (name "unconnected-(U9E-O-Pad10)") (class "Default")
      (node (ref "U9") (pin "10") (pinfunction "O_10") (pintype "output"))
    )
    (net (code "114") (name "unconnected-(U9F-I-Pad13)") (class "Default")
      (node (ref "U9") (pin "13") (pinfunction "I_13") (pintype "input"))
    )
    (net (code "115") (name "unconnected-(U9F-O-Pad12)") (class "Default")
      (node (ref "U9") (pin "12") (pinfunction "O_12") (pintype "output"))
    )
    (net (code "116") (name "unconnected-(U11A-Y2-Pad13)") (class "Default")
      (node (ref "U11") (pin "13") (pinfunction "Y2_13") (pintype "output"))
    )
    (net (code "117") (name "unconnected-(U11A-Y5-Pad10)") (class "Default")
      (node (ref "U11") (pin "10") (pinfunction "Y5_10") (pintype "output"))
    )
    (net (code "118") (name "~{ENABLE_DAVDAK}") (class "Default")
      (node (ref "JP6") (pin "3") (pinfunction "3_3") (pintype "passive"))
      (node (ref "U11") (pin "14") (pinfunction "Y1_14") (pintype "output"))
      (node (ref "U12") (pin "1") (pinfunction "OE_1") (pintype "input"))
      (node (ref "U12") (pin "13") (pinfunction "OE_13") (pintype "input"))
    )
    (net (code "119") (name "~{ENABLE_PIA}") (class "Default")
      (node (ref "JP6") (pin "6") (pinfunction "6_6") (pintype "passive"))
      (node (ref "U1") (pin "23") (pinfunction "23_23") (pintype "passive"))
      (node (ref "U11") (pin "11") (pinfunction "Y4_11") (pintype "output"))
    )
    (net (code "120") (name "~{ENABLE_RAM}") (class "Default")
      (node (ref "JP6") (pin "2") (pinfunction "2_2") (pintype "passive"))
      (node (ref "U11") (pin "15") (pinfunction "Y0_15") (pintype "output"))
      (node (ref "U2") (pin "18") (pinfunction "~{CS}_18") (pintype "input"))
    )
    (net (code "121") (name "~{ENABLE_ROM_C_TO_D}") (class "Default")
      (node (ref "JP6") (pin "8") (pinfunction "8_8") (pintype "passive"))
      (node (ref "U11") (pin "9") (pinfunction "Y6_9") (pintype "output"))
      (node (ref "U12") (pin "10") (pinfunction "OE_10") (pintype "input"))
    )
    (net (code "122") (name "~{ENABLE_ROM_E_TO_F}") (class "Default")
      (node (ref "JP5") (pin "1") (pinfunction "1_1") (pintype "passive"))
      (node (ref "U11") (pin "7") (pinfunction "Y7_7") (pintype "output"))
      (node (ref "U12") (pin "4") (pinfunction "OE_4") (pintype "input"))
    )
    (net (code "123") (name "~{ENABLE_ROM}") (class "Default")
      (node (ref "R12") (pin "2") (pinfunction "2_2") (pintype "passive"))
      (node (ref "U12") (pin "6") (pinfunction "O_6") (pintype "tri_state"))
      (node (ref "U12") (pin "8") (pinfunction "O_8") (pintype "tri_state"))
      (node (ref "U3") (pin "20") (pinfunction "~{CE}_20") (pintype "input"))
    )
    (net (code "124") (name "~{ENABLE_VP931_DATA}") (class "Default")
      (node (ref "JP6") (pin "5") (pinfunction "5_5") (pintype "passive"))
      (node (ref "JP8") (pin "6") (pinfunction "6_6") (pintype "passive"))
      (node (ref "U11") (pin "12") (pinfunction "Y3_12") (pintype "output"))
      (node (ref "U6") (pin "19") (pinfunction "G_19") (pintype "input"))
      (node (ref "U9") (pin "9") (pinfunction "I_9") (pintype "input"))
    )
    (net (code "125") (name "~{E}") (class "Default")
      (node (ref "U10") (pin "2") (pinfunction "D_2") (pintype "input"))
      (node (ref "U10") (pin "8") (pinfunction "~{Q}_8") (pintype "output"))
      (node (ref "U7") (pin "3") (pinfunction "I0_3") (pintype "input"))
    )
    (net (code "126") (name "~{FIRQ}") (class "Default")
      (node (ref "JP1") (pin "4") (pinfunction "4_4") (pintype "passive"))
      (node (ref "R3") (pin "2") (pinfunction "2_2") (pintype "passive"))
      (node (ref "U4") (pin "4") (pinfunction "4_4") (pintype "passive"))
    )
    (net (code "127") (name "~{HALT}") (class "Default")
      (node (ref "JP4") (pin "1") (pinfunction "1_1") (pintype "passive"))
      (node (ref "R4") (pin "2") (pinfunction "2_2") (pintype "passive"))
      (node (ref "U4") (pin "40") (pinfunction "40_40") (pintype "passive"))
    )
    (net (code "128") (name "~{IRQ}") (class "Default")
      (node (ref "JP1") (pin "3") (pinfunction "3_3") (pintype "passive"))
      (node (ref "R6") (pin "2") (pinfunction "2_2") (pintype "passive"))
      (node (ref "U4") (pin "3") (pinfunction "3_3") (pintype "passive"))
    )
    (net (code "129") (name "~{NMI}") (class "Default")
      (node (ref "JP1") (pin "2") (pinfunction "2_2") (pintype "passive"))
      (node (ref "R5") (pin "2") (pinfunction "2_2") (pintype "passive"))
      (node (ref "U4") (pin "2") (pinfunction "2_2") (pintype "passive"))
    )
    (net (code "130") (name "~{Q}") (class "Default")
      (node (ref "U10") (pin "6") (pinfunction "~{Q}_6") (pintype "output"))
      (node (ref "U7") (pin "4") (pinfunction "I1_4") (pintype "input"))
      (node (ref "U7") (pin "5") (pinfunction "I2_5") (pintype "input"))
    )
    (net (code "131") (name "~{RESET}") (class "Default")
      (node (ref "J2") (pin "2") (pinfunction "S_2") (pintype "passive"))
      (node (ref "JP4") (pin "4") (pinfunction "4_4") (pintype "passive"))
      (node (ref "R9") (pin "2") (pinfunction "2_2") (pintype "passive"))
      (node (ref "U1") (pin "34") (pinfunction "34_34") (pintype "passive"))
      (node (ref "U4") (pin "37") (pinfunction "37_37") (pintype "passive"))
    )
    (net (code "132") (name "~{VP931_RDEN}") (class "Default")
      (node (ref "DB1") (pin "P10") (pinfunction "10_P10") (pintype "bidirectional"))
      (node (ref "U7") (pin "12") (pinfunction "O_12") (pintype "output"))
    )
    (net (code "133") (name "~{VP931_WREN}") (class "Default")
      (node (ref "DB1") (pin "P22") (pinfunction "22_P22") (pintype "bidirectional"))
      (node (ref "U7") (pin "8") (pinfunction "O_8") (pintype "output"))
    )
  )
)
